# Antenna_Deployment.net
KiCad netlist of a schematic drawn in Altium Designer
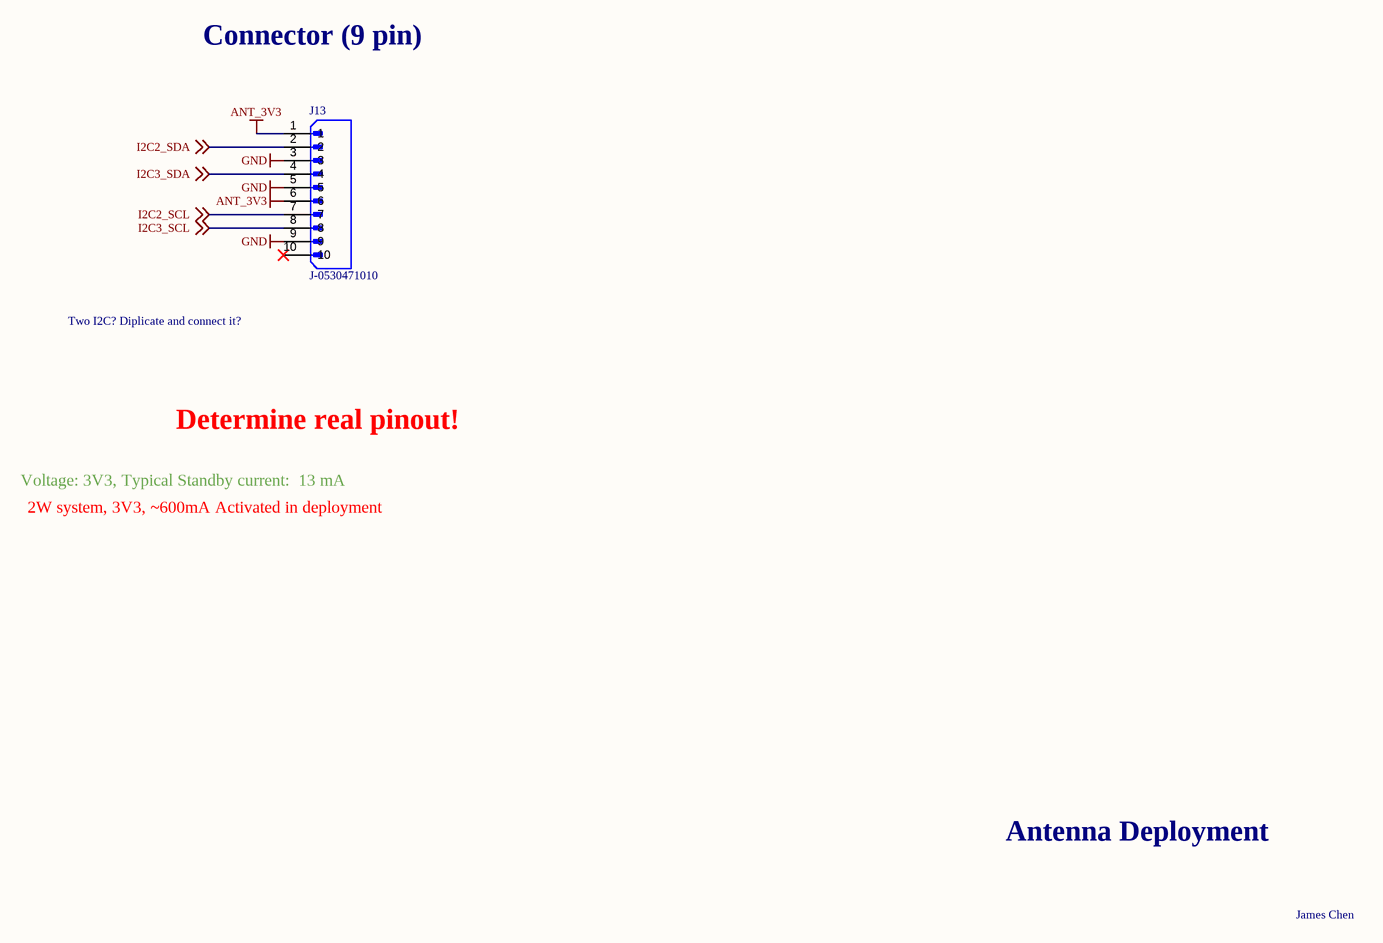
[diagram p0: Antenna Deployment.SchDoc]

(export (version "E")
  (design (tool "Eeschema 10.0.6"))
  (components
    (comp (ref "J13")
      (value "J-0530471010")
      (footprint "J-0530471010")
      (description "CONN HEADER VERT 10POS 1.25MM")
      (fields (field (name "MANUFACTURER") "Molex") (field (name "MANUFACTURER PART #") "0530471010"))
      (libsource (lib "OBC Development Board") (part "J-0530471010"))
    )
  )
  (nets
    (net (code "1") (name "ANT_3V3") (class "Default")
      (node (ref "J13") (pin "1") (pinfunction "1_1") (pintype "passive"))
      (node (ref "J13") (pin "6") (pinfunction "6_6") (pintype "passive"))
    )
    (net (code "2") (name "GND") (class "Default")
      (node (ref "J13") (pin "3") (pinfunction "3_3") (pintype "passive"))
      (node (ref "J13") (pin "5") (pinfunction "5_5") (pintype "passive"))
      (node (ref "J13") (pin "9") (pinfunction "9_9") (pintype "passive"))
    )
    (net (code "3") (name "I2C2_SCL") (class "Default")
      (node (ref "J13") (pin "7") (pinfunction "7_7") (pintype "passive"))
    )
    (net (code "4") (name "I2C2_SDA") (class "Default")
      (node (ref "J13") (pin "2") (pinfunction "2_2") (pintype "passive"))
    )
    (net (code "5") (name "I2C3_SCL") (class "Default")
      (node (ref "J13") (pin "8") (pinfunction "8_8") (pintype "passive"))
    )
    (net (code "6") (name "I2C3_SDA") (class "Default")
      (node (ref "J13") (pin "4") (pinfunction "4_4") (pintype "passive"))
    )
    (net (code "7") (name "unconnected-(J13-Pad10)") (class "Default")
      (node (ref "J13") (pin "10") (pinfunction "10_10") (pintype "passive+no_connect"))
    )
  )
)
